# PLA_Controller_ring_Gen2_Rev2.net
KiCad netlist of a schematic drawn in EAGLE
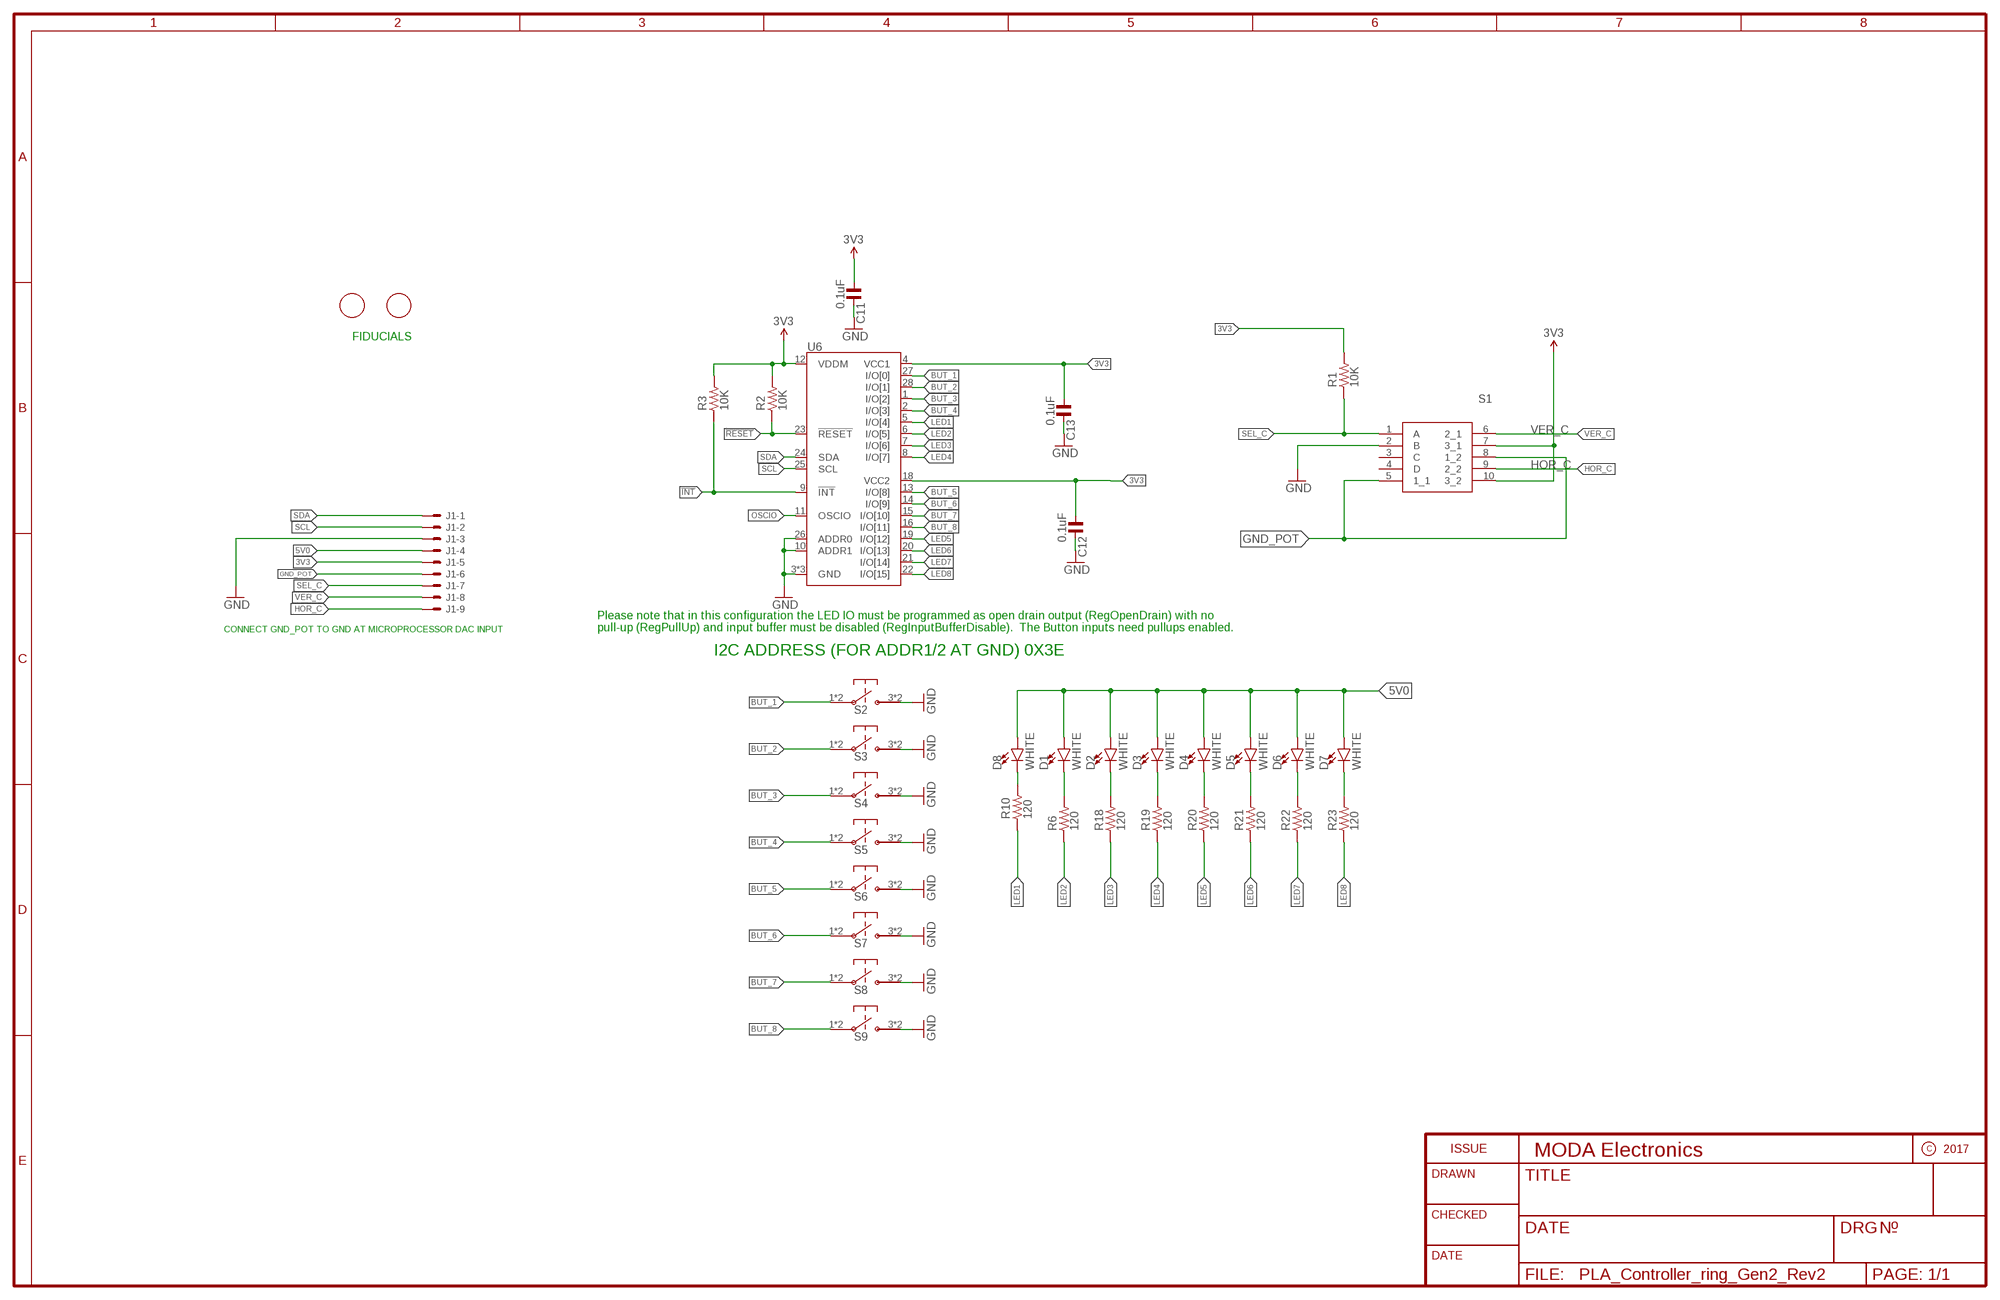
[diagram p0: schematic, sheet 1]

(export (version "E")
  (design (tool "Eeschema 10.0.6"))
  (components
    (comp (ref "C11")
      (value "0.1uF")
      (footprint "eagle-import:C0603")
      (fields (field (name "PARTNO") "CAP-00810"))
      (libsource (lib "eagle-import") (part "C_0603"))
    )
    (comp (ref "C12")
      (value "0.1uF")
      (footprint "eagle-import:C0603")
      (fields (field (name "PARTNO") "CAP-00810"))
      (libsource (lib "eagle-import") (part "C_0603"))
    )
    (comp (ref "C13")
      (value "0.1uF")
      (footprint "eagle-import:C0603")
      (fields (field (name "PARTNO") "CAP-00810"))
      (libsource (lib "eagle-import") (part "C_0603"))
    )
    (comp (ref "D1")
      (value "WHITE")
      (footprint "eagle-import:LED-0603")
      (fields (field (name "PARTNO") "QBLP601-IW"))
      (libsource (lib "eagle-import") (part "LED-WHITE0603"))
    )
    (comp (ref "D2")
      (value "WHITE")
      (footprint "eagle-import:LED-0603")
      (fields (field (name "PARTNO") "QBLP601-IW"))
      (libsource (lib "eagle-import") (part "LED-WHITE0603"))
    )
    (comp (ref "D3")
      (value "WHITE")
      (footprint "eagle-import:LED-0603")
      (fields (field (name "PARTNO") "QBLP601-IW"))
      (libsource (lib "eagle-import") (part "LED-WHITE0603"))
    )
    (comp (ref "D4")
      (value "WHITE")
      (footprint "eagle-import:LED-0603")
      (fields (field (name "PARTNO") "QBLP601-IW"))
      (libsource (lib "eagle-import") (part "LED-WHITE0603"))
    )
    (comp (ref "D5")
      (value "WHITE")
      (footprint "eagle-import:LED-0603")
      (fields (field (name "PARTNO") "QBLP601-IW"))
      (libsource (lib "eagle-import") (part "LED-WHITE0603"))
    )
    (comp (ref "D6")
      (value "WHITE")
      (footprint "eagle-import:LED-0603")
      (fields (field (name "PARTNO") "QBLP601-IW"))
      (libsource (lib "eagle-import") (part "LED-WHITE0603"))
    )
    (comp (ref "D7")
      (value "WHITE")
      (footprint "eagle-import:LED-0603")
      (fields (field (name "PARTNO") "QBLP601-IW"))
      (libsource (lib "eagle-import") (part "LED-WHITE0603"))
    )
    (comp (ref "D8")
      (value "WHITE")
      (footprint "eagle-import:LED-0603")
      (fields (field (name "PARTNO") "QBLP601-IW"))
      (libsource (lib "eagle-import") (part "LED-WHITE0603"))
    )
    (comp (ref "J1")
      (value "BM09B-SRSS-TB")
      (footprint "eagle-import:BM09B-SRSS-TB")
      (fields (field (name "PARTNO") "BM09B-SRSS-TB"))
      (libsource (lib "eagle-import") (part "?M09B-SRSS-TBB"))
    )
    (comp (ref "R1")
      (value "10K")
      (footprint "eagle-import:R0603")
      (fields (field (name "PARTNO") "ERJ-2GEJ103X"))
      (libsource (lib "eagle-import") (part "R_0603"))
    )
    (comp (ref "R2")
      (value "10K")
      (footprint "eagle-import:R0603")
      (fields (field (name "PARTNO") "ERJ-2GEJ103X"))
      (libsource (lib "eagle-import") (part "R_0603"))
    )
    (comp (ref "R3")
      (value "10K")
      (footprint "eagle-import:R0603")
      (fields (field (name "PARTNO") "ERJ-2GEJ103X"))
      (libsource (lib "eagle-import") (part "R_0603"))
    )
    (comp (ref "R6")
      (value "120")
      (footprint "eagle-import:R0603")
      (fields (field (name "PARTNO") "ERJ-PA3J121V"))
      (libsource (lib "eagle-import") (part "R_0603"))
    )
    (comp (ref "R10")
      (value "120")
      (footprint "eagle-import:R0603")
      (fields (field (name "PARTNO") "ERJ-PA3J121V"))
      (libsource (lib "eagle-import") (part "R_0603"))
    )
    (comp (ref "R18")
      (value "120")
      (footprint "eagle-import:R0603")
      (fields (field (name "PARTNO") "ERJ-PA3J121V"))
      (libsource (lib "eagle-import") (part "R_0603"))
    )
    (comp (ref "R19")
      (value "120")
      (footprint "eagle-import:R0603")
      (fields (field (name "PARTNO") "ERJ-PA3J121V"))
      (libsource (lib "eagle-import") (part "R_0603"))
    )
    (comp (ref "R20")
      (value "120")
      (footprint "eagle-import:R0603")
      (fields (field (name "PARTNO") "ERJ-PA3J121V"))
      (libsource (lib "eagle-import") (part "R_0603"))
    )
    (comp (ref "R21")
      (value "120")
      (footprint "eagle-import:R0603")
      (fields (field (name "PARTNO") "ERJ-PA3J121V"))
      (libsource (lib "eagle-import") (part "R_0603"))
    )
    (comp (ref "R22")
      (value "120")
      (footprint "eagle-import:R0603")
      (fields (field (name "PARTNO") "ERJ-PA3J121V"))
      (libsource (lib "eagle-import") (part "R_0603"))
    )
    (comp (ref "R23")
      (value "120")
      (footprint "eagle-import:R0603")
      (fields (field (name "PARTNO") "ERJ-PA3J121V"))
      (libsource (lib "eagle-import") (part "R_0603"))
    )
    (comp (ref "S1")
      (value "RKJXV1224005")
      (footprint "eagle-import:RKJXV1224005")
      (fields
        (field (name "MOUSER_PART_NUMBER") "688-RKJXV1224005")
        (field (name "RS_PART_NUMBER") "1239578")
      )
      (libsource (lib "eagle-import") (part "RKJXV1224005"))
    )
    (comp (ref "S2")
      (value "TL3315NF100Q")
      (footprint "eagle-import:TL3315NF100Q")
      (fields (field (name "MF") "E-Switch"))
      (libsource (lib "eagle-import") (part "TL3315NF100Q"))
    )
    (comp (ref "S3")
      (value "TL3315NF100Q")
      (footprint "eagle-import:TL3315NF100Q")
      (fields (field (name "MF") "E-Switch"))
      (libsource (lib "eagle-import") (part "TL3315NF100Q"))
    )
    (comp (ref "S4")
      (value "TL3315NF100Q")
      (footprint "eagle-import:TL3315NF100Q")
      (fields (field (name "MF") "E-Switch"))
      (libsource (lib "eagle-import") (part "TL3315NF100Q"))
    )
    (comp (ref "S5")
      (value "TL3315NF100Q")
      (footprint "eagle-import:TL3315NF100Q")
      (fields (field (name "MF") "E-Switch"))
      (libsource (lib "eagle-import") (part "TL3315NF100Q"))
    )
    (comp (ref "S6")
      (value "TL3315NF100Q")
      (footprint "eagle-import:TL3315NF100Q")
      (fields (field (name "MF") "E-Switch"))
      (libsource (lib "eagle-import") (part "TL3315NF100Q"))
    )
    (comp (ref "S7")
      (value "TL3315NF100Q")
      (footprint "eagle-import:TL3315NF100Q")
      (fields (field (name "MF") "E-Switch"))
      (libsource (lib "eagle-import") (part "TL3315NF100Q"))
    )
    (comp (ref "S8")
      (value "TL3315NF100Q")
      (footprint "eagle-import:TL3315NF100Q")
      (fields (field (name "MF") "E-Switch"))
      (libsource (lib "eagle-import") (part "TL3315NF100Q"))
    )
    (comp (ref "S9")
      (value "TL3315NF100Q")
      (footprint "eagle-import:TL3315NF100Q")
      (fields (field (name "MF") "E-Switch"))
      (libsource (lib "eagle-import") (part "TL3315NF100Q"))
    )
    (comp (ref "U$8")
      (value "FIDUCIAL")
      (footprint "eagle-import:FIDUCIAL_1MM")
      (libsource (lib "eagle-import") (part "FIDUCIAL"))
    )
    (comp (ref "U$9")
      (value "FIDUCIAL")
      (footprint "eagle-import:FIDUCIAL_1MM")
      (libsource (lib "eagle-import") (part "FIDUCIAL"))
    )
    (comp (ref "U6")
      (value "SX1509")
      (footprint "eagle-import:QFN-28")
      (fields (field (name "PARTNO") "SX1509BIULTRT"))
      (libsource (lib "eagle-import") (part "SX1509"))
    )
  )
  (nets
    (net (code "1") (name "/~{INT}") (class "Default")
      (node (ref "R3") (pin "1") (pinfunction "1_1") (pintype "passive"))
      (node (ref "U6") (pin "9") (pinfunction "~{INT}_9") (pintype "bidirectional"))
    )
    (net (code "2") (name "/~{RESET}") (class "Default")
      (node (ref "R2") (pin "1") (pinfunction "1_1") (pintype "passive"))
      (node (ref "U6") (pin "23") (pinfunction "~{RESET}_23") (pintype "bidirectional"))
    )
    (net (code "3") (name "3V3") (class "Default")
      (node (ref "C11") (pin "1") (pinfunction "1_1") (pintype "passive"))
      (node (ref "C12") (pin "1") (pinfunction "1_1") (pintype "passive"))
      (node (ref "C13") (pin "1") (pinfunction "1_1") (pintype "passive"))
      (node (ref "J1") (pin "5") (pinfunction "S_5") (pintype "passive"))
      (node (ref "R1") (pin "2") (pinfunction "2_2") (pintype "passive"))
      (node (ref "R2") (pin "2") (pinfunction "2_2") (pintype "passive"))
      (node (ref "R3") (pin "2") (pinfunction "2_2") (pintype "passive"))
      (node (ref "S1") (pin "10") (pinfunction "3_2_10") (pintype "bidirectional"))
      (node (ref "S1") (pin "7") (pinfunction "3_1_7") (pintype "bidirectional"))
      (node (ref "U6") (pin "12") (pinfunction "VDDM_12") (pintype "bidirectional"))
      (node (ref "U6") (pin "18") (pinfunction "VCC2_18") (pintype "bidirectional"))
      (node (ref "U6") (pin "4") (pinfunction "VCC1_4") (pintype "bidirectional"))
    )
    (net (code "4") (name "5V0") (class "Default")
      (node (ref "D1") (pin "A") (pinfunction "A_A") (pintype "passive"))
      (node (ref "D2") (pin "A") (pinfunction "A_A") (pintype "passive"))
      (node (ref "D3") (pin "A") (pinfunction "A_A") (pintype "passive"))
      (node (ref "D4") (pin "A") (pinfunction "A_A") (pintype "passive"))
      (node (ref "D5") (pin "A") (pinfunction "A_A") (pintype "passive"))
      (node (ref "D6") (pin "A") (pinfunction "A_A") (pintype "passive"))
      (node (ref "D7") (pin "A") (pinfunction "A_A") (pintype "passive"))
      (node (ref "D8") (pin "A") (pinfunction "A_A") (pintype "passive"))
      (node (ref "J1") (pin "4") (pinfunction "S_4") (pintype "passive"))
    )
    (net (code "5") (name "BUT_1") (class "Default")
      (node (ref "S2") (pin "1") (pinfunction "P$1_1") (pintype "passive"))
      (node (ref "S2") (pin "2") (pinfunction "P$1_2") (pintype "passive"))
      (node (ref "U6") (pin "27") (pinfunction "I/O[0]_27") (pintype "bidirectional"))
    )
    (net (code "6") (name "BUT_2") (class "Default")
      (node (ref "S3") (pin "1") (pinfunction "P$1_1") (pintype "passive"))
      (node (ref "S3") (pin "2") (pinfunction "P$1_2") (pintype "passive"))
      (node (ref "U6") (pin "28") (pinfunction "I/O[1]_28") (pintype "bidirectional"))
    )
    (net (code "7") (name "BUT_3") (class "Default")
      (node (ref "S4") (pin "1") (pinfunction "P$1_1") (pintype "passive"))
      (node (ref "S4") (pin "2") (pinfunction "P$1_2") (pintype "passive"))
      (node (ref "U6") (pin "1") (pinfunction "I/O[2]_1") (pintype "bidirectional"))
    )
    (net (code "8") (name "BUT_4") (class "Default")
      (node (ref "S5") (pin "1") (pinfunction "P$1_1") (pintype "passive"))
      (node (ref "S5") (pin "2") (pinfunction "P$1_2") (pintype "passive"))
      (node (ref "U6") (pin "2") (pinfunction "I/O[3]_2") (pintype "bidirectional"))
    )
    (net (code "9") (name "BUT_5") (class "Default")
      (node (ref "S6") (pin "1") (pinfunction "P$1_1") (pintype "passive"))
      (node (ref "S6") (pin "2") (pinfunction "P$1_2") (pintype "passive"))
      (node (ref "U6") (pin "13") (pinfunction "I/O[8]_13") (pintype "bidirectional"))
    )
    (net (code "10") (name "BUT_6") (class "Default")
      (node (ref "S7") (pin "1") (pinfunction "P$1_1") (pintype "passive"))
      (node (ref "S7") (pin "2") (pinfunction "P$1_2") (pintype "passive"))
      (node (ref "U6") (pin "14") (pinfunction "I/O[9]_14") (pintype "bidirectional"))
    )
    (net (code "11") (name "BUT_7") (class "Default")
      (node (ref "S8") (pin "1") (pinfunction "P$1_1") (pintype "passive"))
      (node (ref "S8") (pin "2") (pinfunction "P$1_2") (pintype "passive"))
      (node (ref "U6") (pin "15") (pinfunction "I/O[10]_15") (pintype "bidirectional"))
    )
    (net (code "12") (name "BUT_8") (class "Default")
      (node (ref "S9") (pin "1") (pinfunction "P$1_1") (pintype "passive"))
      (node (ref "S9") (pin "2") (pinfunction "P$1_2") (pintype "passive"))
      (node (ref "U6") (pin "16") (pinfunction "I/O[11]_16") (pintype "bidirectional"))
    )
    (net (code "13") (name "GND") (class "Default")
      (node (ref "C11") (pin "2") (pinfunction "2_2") (pintype "passive"))
      (node (ref "C12") (pin "2") (pinfunction "2_2") (pintype "passive"))
      (node (ref "C13") (pin "2") (pinfunction "2_2") (pintype "passive"))
      (node (ref "J1") (pin "3") (pinfunction "S_3") (pintype "passive"))
      (node (ref "S1") (pin "2") (pinfunction "B_2") (pintype "bidirectional"))
      (node (ref "S2") (pin "3") (pinfunction "P$2_3") (pintype "passive"))
      (node (ref "S2") (pin "4") (pinfunction "P$2_4") (pintype "passive"))
      (node (ref "S3") (pin "3") (pinfunction "P$2_3") (pintype "passive"))
      (node (ref "S3") (pin "4") (pinfunction "P$2_4") (pintype "passive"))
      (node (ref "S4") (pin "3") (pinfunction "P$2_3") (pintype "passive"))
      (node (ref "S4") (pin "4") (pinfunction "P$2_4") (pintype "passive"))
      (node (ref "S5") (pin "3") (pinfunction "P$2_3") (pintype "passive"))
      (node (ref "S5") (pin "4") (pinfunction "P$2_4") (pintype "passive"))
      (node (ref "S6") (pin "3") (pinfunction "P$2_3") (pintype "passive"))
      (node (ref "S6") (pin "4") (pinfunction "P$2_4") (pintype "passive"))
      (node (ref "S7") (pin "3") (pinfunction "P$2_3") (pintype "passive"))
      (node (ref "S7") (pin "4") (pinfunction "P$2_4") (pintype "passive"))
      (node (ref "S8") (pin "3") (pinfunction "P$2_3") (pintype "passive"))
      (node (ref "S8") (pin "4") (pinfunction "P$2_4") (pintype "passive"))
      (node (ref "S9") (pin "3") (pinfunction "P$2_3") (pintype "passive"))
      (node (ref "S9") (pin "4") (pinfunction "P$2_4") (pintype "passive"))
      (node (ref "U6") (pin "10") (pinfunction "ADDR1_10") (pintype "bidirectional"))
      (node (ref "U6") (pin "17") (pinfunction "GND_17") (pintype "bidirectional"))
      (node (ref "U6") (pin "26") (pinfunction "ADDR0_26") (pintype "bidirectional"))
      (node (ref "U6") (pin "29") (pinfunction "GND_29") (pintype "bidirectional"))
      (node (ref "U6") (pin "3") (pinfunction "GND_3") (pintype "bidirectional"))
    )
    (net (code "14") (name "GND_POT") (class "Default")
      (node (ref "J1") (pin "6") (pinfunction "S_6") (pintype "passive"))
      (node (ref "S1") (pin "5") (pinfunction "1_1_5") (pintype "bidirectional"))
      (node (ref "S1") (pin "8") (pinfunction "1_2_8") (pintype "bidirectional"))
    )
    (net (code "15") (name "HOR_C") (class "Default")
      (node (ref "J1") (pin "9") (pinfunction "S_9") (pintype "passive"))
      (node (ref "S1") (pin "9") (pinfunction "2_2_9") (pintype "bidirectional"))
    )
    (net (code "16") (name "LED1") (class "Default")
      (node (ref "R10") (pin "1") (pinfunction "1_1") (pintype "passive"))
      (node (ref "U6") (pin "5") (pinfunction "I/O[4]_5") (pintype "bidirectional"))
    )
    (net (code "17") (name "LED2") (class "Default")
      (node (ref "R6") (pin "1") (pinfunction "1_1") (pintype "passive"))
      (node (ref "U6") (pin "6") (pinfunction "I/O[5]_6") (pintype "bidirectional"))
    )
    (net (code "18") (name "LED3") (class "Default")
      (node (ref "R18") (pin "1") (pinfunction "1_1") (pintype "passive"))
      (node (ref "U6") (pin "7") (pinfunction "I/O[6]_7") (pintype "bidirectional"))
    )
    (net (code "19") (name "LED4") (class "Default")
      (node (ref "R19") (pin "1") (pinfunction "1_1") (pintype "passive"))
      (node (ref "U6") (pin "8") (pinfunction "I/O[7]_8") (pintype "bidirectional"))
    )
    (net (code "20") (name "LED5") (class "Default")
      (node (ref "R20") (pin "1") (pinfunction "1_1") (pintype "passive"))
      (node (ref "U6") (pin "19") (pinfunction "I/O[12]_19") (pintype "bidirectional"))
    )
    (net (code "21") (name "LED6") (class "Default")
      (node (ref "R21") (pin "1") (pinfunction "1_1") (pintype "passive"))
      (node (ref "U6") (pin "20") (pinfunction "I/O[13]_20") (pintype "bidirectional"))
    )
    (net (code "22") (name "LED7") (class "Default")
      (node (ref "R22") (pin "1") (pinfunction "1_1") (pintype "passive"))
      (node (ref "U6") (pin "21") (pinfunction "I/O[14]_21") (pintype "bidirectional"))
    )
    (net (code "23") (name "LED8") (class "Default")
      (node (ref "R23") (pin "1") (pinfunction "1_1") (pintype "passive"))
      (node (ref "U6") (pin "22") (pinfunction "I/O[15]_22") (pintype "bidirectional"))
    )
    (net (code "24") (name "Net-(D1-PadC)") (class "Default")
      (node (ref "D1") (pin "C") (pinfunction "C_C") (pintype "passive"))
      (node (ref "R6") (pin "2") (pinfunction "2_2") (pintype "passive"))
    )
    (net (code "25") (name "Net-(D2-PadC)") (class "Default")
      (node (ref "D2") (pin "C") (pinfunction "C_C") (pintype "passive"))
      (node (ref "R18") (pin "2") (pinfunction "2_2") (pintype "passive"))
    )
    (net (code "26") (name "Net-(D3-PadC)") (class "Default")
      (node (ref "D3") (pin "C") (pinfunction "C_C") (pintype "passive"))
      (node (ref "R19") (pin "2") (pinfunction "2_2") (pintype "passive"))
    )
    (net (code "27") (name "Net-(D4-PadC)") (class "Default")
      (node (ref "D4") (pin "C") (pinfunction "C_C") (pintype "passive"))
      (node (ref "R20") (pin "2") (pinfunction "2_2") (pintype "passive"))
    )
    (net (code "28") (name "Net-(D5-PadC)") (class "Default")
      (node (ref "D5") (pin "C") (pinfunction "C_C") (pintype "passive"))
      (node (ref "R21") (pin "2") (pinfunction "2_2") (pintype "passive"))
    )
    (net (code "29") (name "Net-(D6-PadC)") (class "Default")
      (node (ref "D6") (pin "C") (pinfunction "C_C") (pintype "passive"))
      (node (ref "R22") (pin "2") (pinfunction "2_2") (pintype "passive"))
    )
    (net (code "30") (name "Net-(D7-PadC)") (class "Default")
      (node (ref "D7") (pin "C") (pinfunction "C_C") (pintype "passive"))
      (node (ref "R23") (pin "2") (pinfunction "2_2") (pintype "passive"))
    )
    (net (code "31") (name "Net-(D8-PadC)") (class "Default")
      (node (ref "D8") (pin "C") (pinfunction "C_C") (pintype "passive"))
      (node (ref "R10") (pin "2") (pinfunction "2_2") (pintype "passive"))
    )
    (net (code "32") (name "OSCIO") (class "Default")
      (node (ref "U6") (pin "11") (pinfunction "OSCIO_11") (pintype "bidirectional"))
    )
    (net (code "33") (name "SCL") (class "Default")
      (node (ref "J1") (pin "2") (pinfunction "S_2") (pintype "passive"))
      (node (ref "U6") (pin "25") (pinfunction "SCL_25") (pintype "bidirectional"))
    )
    (net (code "34") (name "SDA") (class "Default")
      (node (ref "J1") (pin "1") (pinfunction "S_1") (pintype "passive"))
      (node (ref "U6") (pin "24") (pinfunction "SDA_24") (pintype "bidirectional"))
    )
    (net (code "35") (name "SEL_C") (class "Default")
      (node (ref "J1") (pin "7") (pinfunction "S_7") (pintype "passive"))
      (node (ref "R1") (pin "1") (pinfunction "1_1") (pintype "passive"))
      (node (ref "S1") (pin "1") (pinfunction "A_1") (pintype "bidirectional"))
    )
    (net (code "36") (name "VER_C") (class "Default")
      (node (ref "J1") (pin "8") (pinfunction "S_8") (pintype "passive"))
      (node (ref "S1") (pin "6") (pinfunction "2_1_6") (pintype "bidirectional"))
    )
    (net (code "37") (name "unconnected-(S1-C-Pad3)") (class "Default")
      (node (ref "S1") (pin "3") (pinfunction "C_3") (pintype "bidirectional"))
    )
    (net (code "38") (name "unconnected-(S1-D-Pad4)") (class "Default")
      (node (ref "S1") (pin "4") (pinfunction "D_4") (pintype "bidirectional"))
    )
  )
)
